# GSMBoard_SIM900.net
KiCad netlist of a schematic drawn in Altium Designer
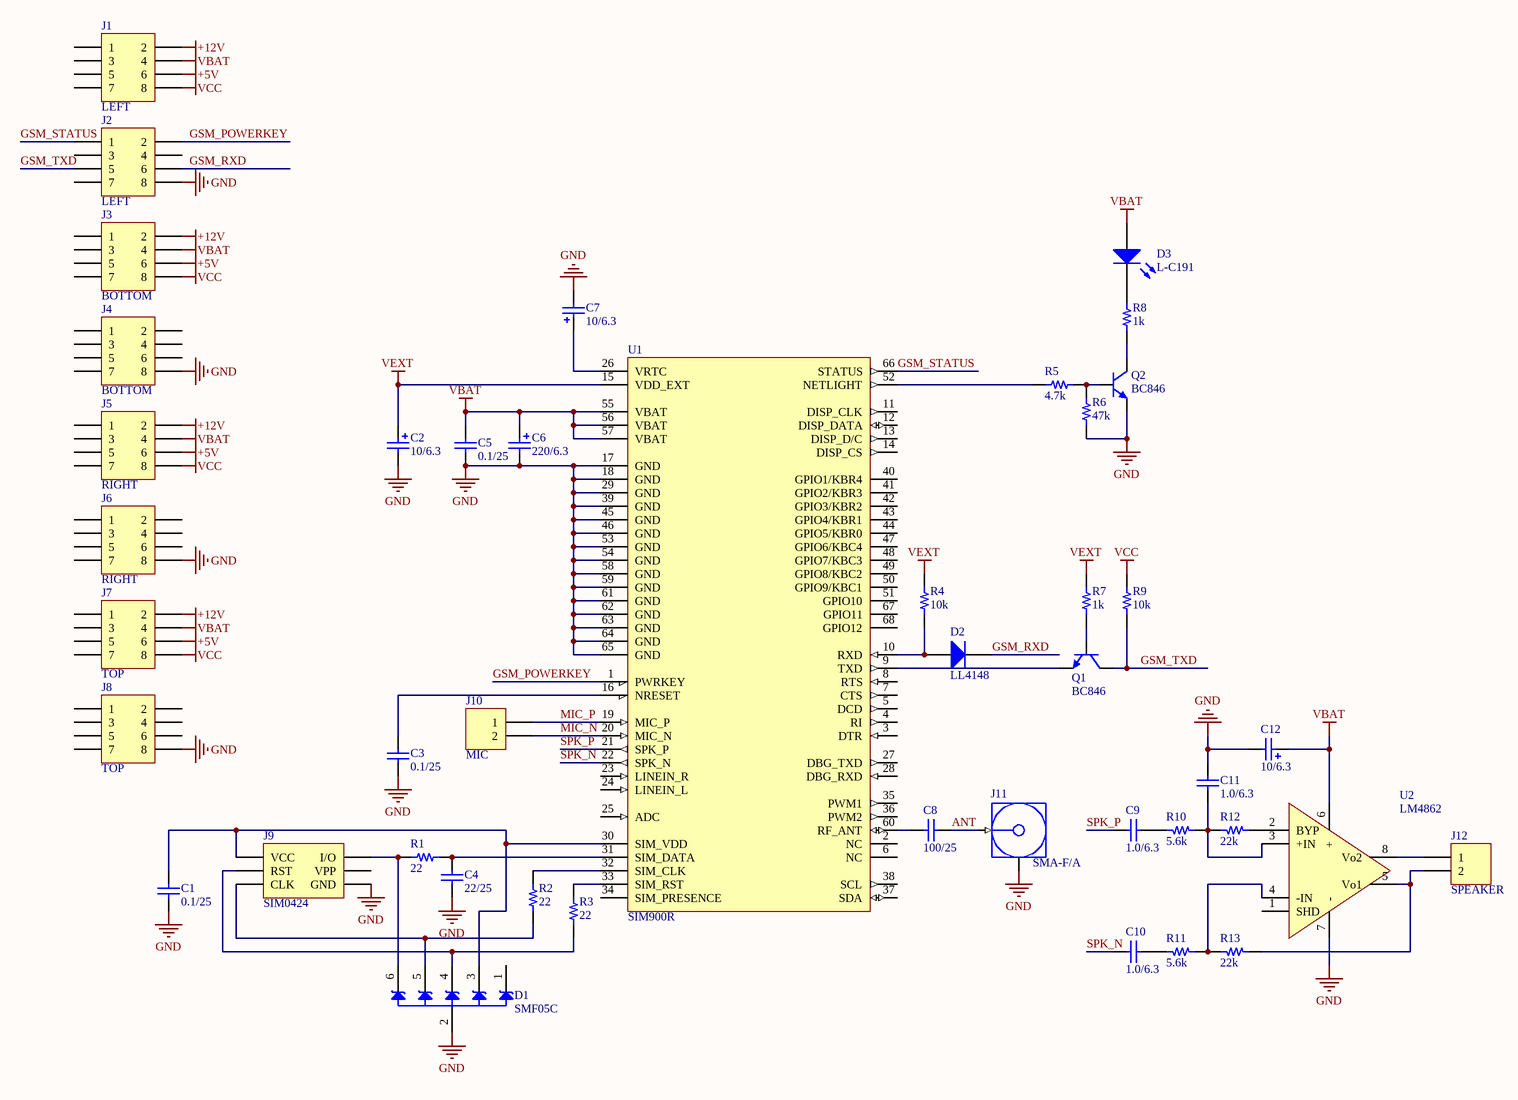
[diagram p0: GSMBoard_SIM900.SchDoc]

(export (version "E")
  (design (tool "Eeschema 10.0.6"))
  (components
    (comp (ref "C1")
      (value "0.1/25")
      (footprint "CAP0402")
      (description "Ceramic chip capacitor 0402")
      (fields
        (field (name "PARTNUMBER") "CAP0402")
        (field (name "VOLTAGE") "25")
        (field (name "AUTHOR") "oiezhov")
      )
      (libsource (lib "Library") (part "Capacitor"))
    )
    (comp (ref "C2")
      (value "10/6.3")
      (footprint "SMA")
      (description "Standard tantalum SMT capacitor, size A")
      (fields
        (field (name "PARTNUMBER") "TAJA")
        (field (name "VOLTAGE") "6.3")
        (field (name "AUTHOR") "oiezhov")
      )
      (libsource (lib "Library") (part "Polar capacitor"))
    )
    (comp (ref "C3")
      (value "0.1/25")
      (footprint "CAP0402")
      (description "Ceramic chip capacitor 0402")
      (fields
        (field (name "PARTNUMBER") "CAP0402")
        (field (name "VOLTAGE") "25")
        (field (name "AUTHOR") "oiezhov")
      )
      (libsource (lib "Library") (part "Capacitor"))
    )
    (comp (ref "C4")
      (value "22/25")
      (footprint "CAP0402")
      (description "Ceramic chip capacitor 0402")
      (fields
        (field (name "PARTNUMBER") "CAP0402")
        (field (name "VOLTAGE") "25")
        (field (name "AUTHOR") "oiezhov")
      )
      (libsource (lib "Library") (part "Capacitor"))
    )
    (comp (ref "C5")
      (value "0.1/25")
      (footprint "CAP0402")
      (description "Ceramic chip capacitor 0402")
      (fields
        (field (name "PARTNUMBER") "CAP0402")
        (field (name "VOLTAGE") "25")
        (field (name "AUTHOR") "oiezhov")
      )
      (libsource (lib "Library") (part "Capacitor"))
    )
    (comp (ref "C6")
      (value "220/6.3")
      (footprint "SMC")
      (description "Standard tantalum SMT capacitor, size C")
      (fields
        (field (name "PARTNUMBER") "TAJC")
        (field (name "VOLTAGE") "6.3")
        (field (name "AUTHOR") "oiezhov")
      )
      (libsource (lib "Library") (part "Polar capacitor"))
    )
    (comp (ref "C7")
      (value "10/6.3")
      (footprint "SMA")
      (description "Standard tantalum SMT capacitor, size A")
      (fields
        (field (name "PARTNUMBER") "TAJA")
        (field (name "VOLTAGE") "6.3")
        (field (name "AUTHOR") "oiezhov")
      )
      (libsource (lib "Library") (part "Polar capacitor"))
    )
    (comp (ref "C8")
      (value "100/25")
      (footprint "CAP0402")
      (description "Ceramic chip capacitor 0402")
      (fields
        (field (name "PARTNUMBER") "CAP0402")
        (field (name "VOLTAGE") "25")
        (field (name "AUTHOR") "oiezhov")
      )
      (libsource (lib "Library") (part "Capacitor"))
    )
    (comp (ref "C9")
      (value "1.0/6.3")
      (footprint "CAP0402")
      (description "Ceramic chip capacitor 0402")
      (fields
        (field (name "PARTNUMBER") "CAP0402")
        (field (name "VOLTAGE") "6.3")
        (field (name "AUTHOR") "oiezhov")
      )
      (libsource (lib "Library") (part "Capacitor"))
    )
    (comp (ref "C10")
      (value "1.0/6.3")
      (footprint "CAP0402")
      (description "Ceramic chip capacitor 0402")
      (fields
        (field (name "PARTNUMBER") "CAP0402")
        (field (name "VOLTAGE") "6.3")
        (field (name "AUTHOR") "oiezhov")
      )
      (libsource (lib "Library") (part "Capacitor"))
    )
    (comp (ref "C11")
      (value "1.0/6.3")
      (footprint "CAP0402")
      (description "Ceramic chip capacitor 0402")
      (fields
        (field (name "PARTNUMBER") "CAP0402")
        (field (name "VOLTAGE") "6.3")
        (field (name "AUTHOR") "oiezhov")
      )
      (libsource (lib "Library") (part "Capacitor"))
    )
    (comp (ref "C12")
      (value "10/6.3")
      (footprint "SMA")
      (description "Standard tantalum SMT capacitor, size A")
      (fields
        (field (name "PARTNUMBER") "TAJA")
        (field (name "VOLTAGE") "6.3")
        (field (name "AUTHOR") "oiezhov")
      )
      (libsource (lib "Library") (part "Polar capacitor"))
    )
    (comp (ref "D1")
      (value "SMF05C")
      (footprint "SOT363")
      (description "5-line TVS Array for ESD and Latch-Up Protection")
      (fields (field (name "AUTHOR") "oiezhov"))
      (libsource (lib "Library") (part "5x TVS array"))
    )
    (comp (ref "D2")
      (value "LL4148")
      (footprint "SOD80")
      (description "Small Signal Diode")
      (fields (field (name "AUTHOR") "oiezhov"))
      (libsource (lib "Library") (part "Diode"))
    )
    (comp (ref "D3")
      (value "L-C191")
      (footprint "LED0603")
      (description "SMD LED, size 0603")
      (fields (field (name "AUTHOR") "oiezhov"))
      (libsource (lib "Library") (part "LED"))
    )
    (comp (ref "J1")
      (value "LEFT")
      (footprint "PBDM-8")
      (description "2x4-pin header, pitch 2.54 mm")
      (fields (field (name "PARTNUMBER") "PBDM-8") (field (name "AUTHOR") "oiezhov"))
      (libsource (lib "Library") (part "8-pin dual row connector"))
    )
    (comp (ref "J2")
      (value "LEFT")
      (footprint "PBDM-8")
      (description "2x4-pin header, pitch 2.54 mm")
      (fields (field (name "PARTNUMBER") "PBDM-8") (field (name "AUTHOR") "oiezhov"))
      (libsource (lib "Library") (part "8-pin dual row connector"))
    )
    (comp (ref "J3")
      (value "BOTTOM")
      (footprint "PBDM-8")
      (description "2x4-pin header, pitch 2.54 mm")
      (fields (field (name "PARTNUMBER") "PBDM-8") (field (name "AUTHOR") "oiezhov"))
      (libsource (lib "Library") (part "8-pin dual row connector"))
    )
    (comp (ref "J4")
      (value "BOTTOM")
      (footprint "PBDM-8")
      (description "2x4-pin header, pitch 2.54 mm")
      (fields (field (name "PARTNUMBER") "PBDM-8") (field (name "AUTHOR") "oiezhov"))
      (libsource (lib "Library") (part "8-pin dual row connector"))
    )
    (comp (ref "J5")
      (value "RIGHT")
      (footprint "PBDM-8")
      (description "2x4-pin header, pitch 2.54 mm")
      (fields (field (name "PARTNUMBER") "PBDM-8") (field (name "AUTHOR") "oiezhov"))
      (libsource (lib "Library") (part "8-pin dual row connector"))
    )
    (comp (ref "J6")
      (value "RIGHT")
      (footprint "PBDM-8")
      (description "2x4-pin header, pitch 2.54 mm")
      (fields (field (name "PARTNUMBER") "PBDM-8") (field (name "AUTHOR") "oiezhov"))
      (libsource (lib "Library") (part "8-pin dual row connector"))
    )
    (comp (ref "J7")
      (value "TOP")
      (footprint "PBDM-8")
      (description "2x4-pin header, pitch 2.54 mm")
      (fields (field (name "PARTNUMBER") "PBDM-8") (field (name "AUTHOR") "oiezhov"))
      (libsource (lib "Library") (part "8-pin dual row connector"))
    )
    (comp (ref "J8")
      (value "TOP")
      (footprint "PBDM-8")
      (description "2x4-pin header, pitch 2.54 mm")
      (fields (field (name "PARTNUMBER") "PBDM-8") (field (name "AUTHOR") "oiezhov"))
      (libsource (lib "Library") (part "8-pin dual row connector"))
    )
    (comp (ref "J9")
      (value "SIM0424")
      (footprint "SIM0424")
      (description "6-pin SIM card holder")
      (fields (field (name "AUTHOR") "oiezhov"))
      (libsource (lib "Library") (part "6-pin SIM holder"))
    )
    (comp (ref "J10")
      (value "MIC")
      (footprint "PLS-2R")
      (description "2-pin angle header, pitch 2.54 mm")
      (fields (field (name "PARTNUMBER") "PLS-2R") (field (name "AUTHOR") "oiezhov"))
      (libsource (lib "") (part "2-pin connector_1"))
    )
    (comp (ref "J11")
      (value "SMA-F/A")
      (footprint "SMA-F/A")
      (description "Angle SMA female connector")
      (fields (field (name "AUTHOR") "oiezhov"))
      (libsource (lib "Library") (part "SMA"))
    )
    (comp (ref "J12")
      (value "SPEAKER")
      (footprint "PLS-2R")
      (description "2-pin angle header, pitch 2.54 mm")
      (fields (field (name "PARTNUMBER") "PLS-2R") (field (name "AUTHOR") "oiezhov"))
      (libsource (lib "Library") (part "2-pin connector"))
    )
    (comp (ref "Q1")
      (value "BC846")
      (footprint "SOT23")
      (description "NPN Silicon AF Transistor")
      (fields (field (name "AUTHOR") "oiezhov"))
      (libsource (lib "Library") (part "NPN Transistor (B-E-C)"))
    )
    (comp (ref "Q2")
      (value "BC846")
      (footprint "SOT23")
      (description "NPN Silicon AF Transistor")
      (fields (field (name "AUTHOR") "oiezhov"))
      (libsource (lib "Library") (part "NPN Transistor (B-E-C)"))
    )
    (comp (ref "R1")
      (value "22")
      (footprint "RES0402")
      (description "Ceramic chip resistor")
      (fields (field (name "PARTNUMBER") "RES0402") (field (name "AUTHOR") "oiezhov"))
      (libsource (lib "Library") (part "Resistor"))
    )
    (comp (ref "R2")
      (value "22")
      (footprint "RES0402")
      (description "Ceramic chip resistor")
      (fields (field (name "PARTNUMBER") "RES0402") (field (name "AUTHOR") "oiezhov"))
      (libsource (lib "Library") (part "Resistor"))
    )
    (comp (ref "R3")
      (value "22")
      (footprint "RES0402")
      (description "Ceramic chip resistor")
      (fields (field (name "PARTNUMBER") "RES0402") (field (name "AUTHOR") "oiezhov"))
      (libsource (lib "Library") (part "Resistor"))
    )
    (comp (ref "R4")
      (value "10k")
      (footprint "RES0402")
      (description "Ceramic chip resistor")
      (fields (field (name "PARTNUMBER") "RES0402") (field (name "AUTHOR") "oiezhov"))
      (libsource (lib "Library") (part "Resistor"))
    )
    (comp (ref "R5")
      (value "4.7k")
      (footprint "RES0402")
      (description "Ceramic chip resistor")
      (fields (field (name "PARTNUMBER") "RES0402") (field (name "AUTHOR") "oiezhov"))
      (libsource (lib "Library") (part "Resistor"))
    )
    (comp (ref "R6")
      (value "47k")
      (footprint "RES0402")
      (description "Ceramic chip resistor")
      (fields (field (name "PARTNUMBER") "RES0402") (field (name "AUTHOR") "oiezhov"))
      (libsource (lib "Library") (part "Resistor"))
    )
    (comp (ref "R7")
      (value "1k")
      (footprint "RES0402")
      (description "Ceramic chip resistor")
      (fields (field (name "PARTNUMBER") "RES0402") (field (name "AUTHOR") "oiezhov"))
      (libsource (lib "Library") (part "Resistor"))
    )
    (comp (ref "R8")
      (value "1k")
      (footprint "RES0402")
      (description "Ceramic chip resistor")
      (fields (field (name "PARTNUMBER") "RES0402") (field (name "AUTHOR") "oiezhov"))
      (libsource (lib "Library") (part "Resistor"))
    )
    (comp (ref "R9")
      (value "10k")
      (footprint "RES0402")
      (description "Ceramic chip resistor")
      (fields (field (name "PARTNUMBER") "RES0402") (field (name "AUTHOR") "oiezhov"))
      (libsource (lib "Library") (part "Resistor"))
    )
    (comp (ref "R10")
      (value "5.6k")
      (footprint "RES0402")
      (description "Ceramic chip resistor")
      (fields (field (name "PARTNUMBER") "RES0402") (field (name "AUTHOR") "oiezhov"))
      (libsource (lib "Library") (part "Resistor"))
    )
    (comp (ref "R11")
      (value "5.6k")
      (footprint "RES0402")
      (description "Ceramic chip resistor")
      (fields (field (name "PARTNUMBER") "RES0402") (field (name "AUTHOR") "oiezhov"))
      (libsource (lib "Library") (part "Resistor"))
    )
    (comp (ref "R12")
      (value "22k")
      (footprint "RES0402")
      (description "Ceramic chip resistor")
      (fields (field (name "PARTNUMBER") "RES0402") (field (name "AUTHOR") "oiezhov"))
      (libsource (lib "Library") (part "Resistor"))
    )
    (comp (ref "R13")
      (value "22k")
      (footprint "RES0402")
      (description "Ceramic chip resistor")
      (fields (field (name "PARTNUMBER") "RES0402") (field (name "AUTHOR") "oiezhov"))
      (libsource (lib "Library") (part "Resistor"))
    )
    (comp (ref "U1")
      (value "SIM900R")
      (footprint "SIM900_quad68")
      (description "GSM module; 2G; 1800MHz,900MHz; 85.6kbps; I2C, UART; 3.4A@4.5VDC")
      (fields (field (name "AUTHOR") "oiezhov"))
      (libsource (lib "Library") (part "SIM900"))
    )
    (comp (ref "U2")
      (value "LM4862")
      (footprint "SO8")
      (description "Audio Power Amplifier with Shutdown Mode")
      (fields (field (name "AUTHOR") "oiezhov"))
      (libsource (lib "Library") (part "LM4862"))
    )
  )
  (nets
    (net (code "1") (name "+5V") (class "Default")
      (node (ref "J1") (pin "6") (pinfunction "6_6") (pintype "passive"))
      (node (ref "J3") (pin "6") (pinfunction "6_6") (pintype "passive"))
      (node (ref "J5") (pin "6") (pinfunction "6_6") (pintype "passive"))
      (node (ref "J7") (pin "6") (pinfunction "6_6") (pintype "passive"))
    )
    (net (code "2") (name "+12V") (class "Default")
      (node (ref "J1") (pin "2") (pinfunction "2_2") (pintype "passive"))
      (node (ref "J3") (pin "2") (pinfunction "2_2") (pintype "passive"))
      (node (ref "J5") (pin "2") (pinfunction "2_2") (pintype "passive"))
      (node (ref "J7") (pin "2") (pinfunction "2_2") (pintype "passive"))
    )
    (net (code "3") (name "/ANT") (class "Default")
      (node (ref "C8") (pin "2") (pinfunction "2_2") (pintype "passive"))
      (node (ref "J11") (pin "1") (pinfunction "Signal_1") (pintype "input"))
    )
    (net (code "4") (name "/GSM_POWERKEY") (class "Default")
      (node (ref "J2") (pin "2") (pinfunction "2_2") (pintype "passive"))
      (node (ref "U1") (pin "1") (pinfunction "PWRKEY_1") (pintype "passive"))
    )
    (net (code "5") (name "/GSM_RXD") (class "Default")
      (node (ref "D2") (pin "1") (pinfunction "1_1") (pintype "passive"))
      (node (ref "J2") (pin "6") (pinfunction "6_6") (pintype "passive"))
    )
    (net (code "6") (name "/GSM_STATUS") (class "Default")
      (node (ref "J2") (pin "1") (pinfunction "1_1") (pintype "passive"))
      (node (ref "U1") (pin "66") (pinfunction "STATUS_66") (pintype "output"))
    )
    (net (code "7") (name "/GSM_TXD") (class "Default")
      (node (ref "J2") (pin "5") (pinfunction "5_5") (pintype "passive"))
      (node (ref "Q1") (pin "3") (pinfunction "3_3") (pintype "passive"))
      (node (ref "R9") (pin "2") (pinfunction "2_2") (pintype "passive"))
    )
    (net (code "8") (name "/MIC_N") (class "Default")
      (node (ref "J10") (pin "2") (pinfunction "2_2") (pintype "passive"))
      (node (ref "U1") (pin "20") (pinfunction "MIC_N_20") (pintype "input"))
    )
    (net (code "9") (name "/MIC_P") (class "Default")
      (node (ref "J10") (pin "1") (pinfunction "1_1") (pintype "passive"))
      (node (ref "U1") (pin "19") (pinfunction "MIC_P_19") (pintype "input"))
    )
    (net (code "10") (name "/SPK_N") (class "Default")
      (node (ref "C10") (pin "1") (pinfunction "1_1") (pintype "passive"))
      (node (ref "U1") (pin "22") (pinfunction "SPK_N_22") (pintype "output"))
    )
    (net (code "11") (name "/SPK_P") (class "Default")
      (node (ref "C9") (pin "1") (pinfunction "1_1") (pintype "passive"))
      (node (ref "U1") (pin "21") (pinfunction "SPK_P_21") (pintype "output"))
    )
    (net (code "12") (name "GND") (class "Default")
      (node (ref "C1") (pin "1") (pinfunction "1_1") (pintype "passive"))
      (node (ref "C11") (pin "1") (pinfunction "1_1") (pintype "passive"))
      (node (ref "C12") (pin "1") (pinfunction "1_1") (pintype "passive"))
      (node (ref "C2") (pin "1") (pinfunction "1_1") (pintype "passive"))
      (node (ref "C3") (pin "1") (pinfunction "1_1") (pintype "passive"))
      (node (ref "C4") (pin "1") (pinfunction "1_1") (pintype "passive"))
      (node (ref "C5") (pin "1") (pinfunction "1_1") (pintype "passive"))
      (node (ref "C6") (pin "1") (pinfunction "1_1") (pintype "passive"))
      (node (ref "C7") (pin "1") (pinfunction "1_1") (pintype "passive"))
      (node (ref "D1") (pin "2") (pinfunction "2_2") (pintype "passive"))
      (node (ref "J11") (pin "2") (pinfunction "GND_2") (pintype "power_in"))
      (node (ref "J2") (pin "8") (pinfunction "8_8") (pintype "passive"))
      (node (ref "J4") (pin "8") (pinfunction "8_8") (pintype "passive"))
      (node (ref "J6") (pin "8") (pinfunction "8_8") (pintype "passive"))
      (node (ref "J8") (pin "8") (pinfunction "8_8") (pintype "passive"))
      (node (ref "J9") (pin "4") (pinfunction "GND_4") (pintype "passive"))
      (node (ref "Q2") (pin "2") (pinfunction "2_2") (pintype "passive"))
      (node (ref "R6") (pin "2") (pinfunction "2_2") (pintype "passive"))
      (node (ref "U1") (pin "17") (pinfunction "GND_17") (pintype "passive"))
      (node (ref "U1") (pin "18") (pinfunction "GND_18") (pintype "passive"))
      (node (ref "U1") (pin "29") (pinfunction "GND_29") (pintype "passive"))
      (node (ref "U1") (pin "39") (pinfunction "GND_39") (pintype "passive"))
      (node (ref "U1") (pin "45") (pinfunction "GND_45") (pintype "passive"))
      (node (ref "U1") (pin "46") (pinfunction "GND_46") (pintype "passive"))
      (node (ref "U1") (pin "53") (pinfunction "GND_53") (pintype "passive"))
      (node (ref "U1") (pin "54") (pinfunction "GND_54") (pintype "passive"))
      (node (ref "U1") (pin "58") (pinfunction "GND_58") (pintype "passive"))
      (node (ref "U1") (pin "59") (pinfunction "GND_59") (pintype "passive"))
      (node (ref "U1") (pin "61") (pinfunction "GND_61") (pintype "passive"))
      (node (ref "U1") (pin "62") (pinfunction "GND_62") (pintype "passive"))
      (node (ref "U1") (pin "63") (pinfunction "GND_63") (pintype "passive"))
      (node (ref "U1") (pin "64") (pinfunction "GND_64") (pintype "passive"))
      (node (ref "U1") (pin "65") (pinfunction "GND_65") (pintype "passive"))
      (node (ref "U2") (pin "7") (pinfunction "-_7") (pintype "power_in"))
    )
    (net (code "13") (name "Net-(C9-Pad2)") (class "Default")
      (node (ref "C9") (pin "2") (pinfunction "2_2") (pintype "passive"))
      (node (ref "R10") (pin "2") (pinfunction "2_2") (pintype "passive"))
    )
    (net (code "14") (name "Net-(C10-Pad2)") (class "Default")
      (node (ref "C10") (pin "2") (pinfunction "2_2") (pintype "passive"))
      (node (ref "R11") (pin "2") (pinfunction "2_2") (pintype "passive"))
    )
    (net (code "15") (name "Net-(D3-Pad1)") (class "Default")
      (node (ref "D3") (pin "1") (pinfunction "1_1") (pintype "passive"))
      (node (ref "R8") (pin "1") (pinfunction "1_1") (pintype "passive"))
    )
    (net (code "16") (name "Net-(J9-CLK)") (class "Default")
      (node (ref "D1") (pin "5") (pinfunction "5_5") (pintype "passive"))
      (node (ref "J9") (pin "3") (pinfunction "CLK_3") (pintype "passive"))
      (node (ref "R2") (pin "2") (pinfunction "2_2") (pintype "passive"))
    )
    (net (code "17") (name "Net-(J9-I{slash}O)") (class "Default")
      (node (ref "D1") (pin "6") (pinfunction "6_6") (pintype "passive"))
      (node (ref "J9") (pin "6") (pinfunction "I/O_6") (pintype "passive"))
      (node (ref "R1") (pin "2") (pinfunction "2_2") (pintype "passive"))
    )
    (net (code "18") (name "Net-(J9-RST)") (class "Default")
      (node (ref "D1") (pin "4") (pinfunction "4_4") (pintype "passive"))
      (node (ref "J9") (pin "2") (pinfunction "RST_2") (pintype "passive"))
      (node (ref "R3") (pin "2") (pinfunction "2_2") (pintype "passive"))
    )
    (net (code "19") (name "Net-(J9-VCC)") (class "Default")
      (node (ref "C1") (pin "2") (pinfunction "2_2") (pintype "passive"))
      (node (ref "D1") (pin "3") (pinfunction "3_3") (pintype "passive"))
      (node (ref "J9") (pin "1") (pinfunction "VCC_1") (pintype "passive"))
      (node (ref "U1") (pin "30") (pinfunction "SIM_VDD_30") (pintype "passive"))
    )
    (net (code "20") (name "Net-(Q1-Pad1)") (class "Default")
      (node (ref "Q1") (pin "1") (pinfunction "1_1") (pintype "passive"))
      (node (ref "R7") (pin "2") (pinfunction "2_2") (pintype "passive"))
    )
    (net (code "21") (name "Net-(Q2-Pad1)") (class "Default")
      (node (ref "Q2") (pin "1") (pinfunction "1_1") (pintype "passive"))
      (node (ref "R5") (pin "1") (pinfunction "1_1") (pintype "passive"))
      (node (ref "R6") (pin "1") (pinfunction "1_1") (pintype "passive"))
    )
    (net (code "22") (name "Net-(Q2-Pad3)") (class "Default")
      (node (ref "Q2") (pin "3") (pinfunction "3_3") (pintype "passive"))
      (node (ref "R8") (pin "2") (pinfunction "2_2") (pintype "passive"))
    )
    (net (code "23") (name "Net-(U1-NETLIGHT)") (class "Default")
      (node (ref "R5") (pin "2") (pinfunction "2_2") (pintype "passive"))
      (node (ref "U1") (pin "52") (pinfunction "NETLIGHT_52") (pintype "output"))
    )
    (net (code "24") (name "Net-(U1-NRESET)") (class "Default")
      (node (ref "C3") (pin "2") (pinfunction "2_2") (pintype "passive"))
      (node (ref "U1") (pin "16") (pinfunction "NRESET_16") (pintype "passive"))
    )
    (net (code "25") (name "Net-(U1-RF_ANT)") (class "Default")
      (node (ref "C8") (pin "1") (pinfunction "1_1") (pintype "passive"))
      (node (ref "U1") (pin "60") (pinfunction "RF_ANT_60") (pintype "bidirectional"))
    )
    (net (code "26") (name "Net-(U1-RXD)") (class "Default")
      (node (ref "D2") (pin "2") (pinfunction "2_2") (pintype "passive"))
      (node (ref "R4") (pin "2") (pinfunction "2_2") (pintype "passive"))
      (node (ref "U1") (pin "10") (pinfunction "RXD_10") (pintype "input"))
    )
    (net (code "27") (name "Net-(U1-SIM_CLK)") (class "Default")
      (node (ref "R2") (pin "1") (pinfunction "1_1") (pintype "passive"))
      (node (ref "U1") (pin "32") (pinfunction "SIM_CLK_32") (pintype "passive"))
    )
    (net (code "28") (name "Net-(U1-SIM_DATA)") (class "Default")
      (node (ref "C4") (pin "2") (pinfunction "2_2") (pintype "passive"))
      (node (ref "R1") (pin "1") (pinfunction "1_1") (pintype "passive"))
      (node (ref "U1") (pin "31") (pinfunction "SIM_DATA_31") (pintype "passive"))
    )
    (net (code "29") (name "Net-(U1-SIM_RST)") (class "Default")
      (node (ref "R3") (pin "1") (pinfunction "1_1") (pintype "passive"))
      (node (ref "U1") (pin "33") (pinfunction "SIM_RST_33") (pintype "passive"))
    )
    (net (code "30") (name "Net-(U1-TXD)") (class "Default")
      (node (ref "Q1") (pin "2") (pinfunction "2_2") (pintype "passive"))
      (node (ref "U1") (pin "9") (pinfunction "TXD_9") (pintype "output"))
    )
    (net (code "31") (name "Net-(U1-VRTC)") (class "Default")
      (node (ref "C7") (pin "2") (pinfunction "2_2") (pintype "passive"))
      (node (ref "U1") (pin "26") (pinfunction "VRTC_26") (pintype "power_in"))
    )
    (net (code "32") (name "Net-(U2-+IN)") (class "Default")
      (node (ref "C11") (pin "2") (pinfunction "2_2") (pintype "passive"))
      (node (ref "R10") (pin "1") (pinfunction "1_1") (pintype "passive"))
      (node (ref "R12") (pin "2") (pinfunction "2_2") (pintype "passive"))
      (node (ref "U2") (pin "3") (pinfunction "+IN_3") (pintype "passive"))
    )
    (net (code "33") (name "Net-(U2--IN)") (class "Default")
      (node (ref "R11") (pin "1") (pinfunction "1_1") (pintype "passive"))
      (node (ref "R13") (pin "2") (pinfunction "2_2") (pintype "passive"))
      (node (ref "U2") (pin "4") (pinfunction "-IN_4") (pintype "passive"))
    )
    (net (code "34") (name "Net-(U2-BYP)") (class "Default")
      (node (ref "R12") (pin "1") (pinfunction "1_1") (pintype "passive"))
      (node (ref "U2") (pin "2") (pinfunction "BYP_2") (pintype "passive"))
    )
    (net (code "35") (name "Net-(U2-Vo1)") (class "Default")
      (node (ref "J12") (pin "2") (pinfunction "2_2") (pintype "passive"))
      (node (ref "R13") (pin "1") (pinfunction "1_1") (pintype "passive"))
      (node (ref "U2") (pin "5") (pinfunction "Vo1_5") (pintype "passive"))
    )
    (net (code "36") (name "Net-(U2-Vo2)") (class "Default")
      (node (ref "J12") (pin "1") (pinfunction "1_1") (pintype "passive"))
      (node (ref "U2") (pin "8") (pinfunction "Vo2_8") (pintype "passive"))
    )
    (net (code "37") (name "VBAT") (class "Default")
      (node (ref "C12") (pin "2") (pinfunction "2_2") (pintype "passive"))
      (node (ref "C5") (pin "2") (pinfunction "2_2") (pintype "passive"))
      (node (ref "C6") (pin "2") (pinfunction "2_2") (pintype "passive"))
      (node (ref "D3") (pin "2") (pinfunction "2_2") (pintype "passive"))
      (node (ref "J1") (pin "4") (pinfunction "4_4") (pintype "passive"))
      (node (ref "J3") (pin "4") (pinfunction "4_4") (pintype "passive"))
      (node (ref "J5") (pin "4") (pinfunction "4_4") (pintype "passive"))
      (node (ref "J7") (pin "4") (pinfunction "4_4") (pintype "passive"))
      (node (ref "U1") (pin "55") (pinfunction "VBAT_55") (pintype "power_in"))
      (node (ref "U1") (pin "56") (pinfunction "VBAT_56") (pintype "power_in"))
      (node (ref "U1") (pin "57") (pinfunction "VBAT_57") (pintype "power_in"))
      (node (ref "U2") (pin "6") (pinfunction "+_6") (pintype "power_in"))
    )
    (net (code "38") (name "VCC") (class "Default")
      (node (ref "J1") (pin "8") (pinfunction "8_8") (pintype "passive"))
      (node (ref "J3") (pin "8") (pinfunction "8_8") (pintype "passive"))
      (node (ref "J5") (pin "8") (pinfunction "8_8") (pintype "passive"))
      (node (ref "J7") (pin "8") (pinfunction "8_8") (pintype "passive"))
      (node (ref "R9") (pin "1") (pinfunction "1_1") (pintype "passive"))
    )
    (net (code "39") (name "VEXT") (class "Default")
      (node (ref "C2") (pin "2") (pinfunction "2_2") (pintype "passive"))
      (node (ref "R4") (pin "1") (pinfunction "1_1") (pintype "passive"))
      (node (ref "R7") (pin "1") (pinfunction "1_1") (pintype "passive"))
      (node (ref "U1") (pin "15") (pinfunction "VDD_EXT_15") (pintype "power_in"))
    )
    (net (code "40") (name "unconnected-(D1-Pad1)") (class "Default")
      (node (ref "D1") (pin "1") (pinfunction "1_1") (pintype "passive"))
    )
    (net (code "41") (name "unconnected-(J1-Pad1)") (class "Default")
      (node (ref "J1") (pin "1") (pinfunction "1_1") (pintype "passive"))
    )
    (net (code "42") (name "unconnected-(J1-Pad3)") (class "Default")
      (node (ref "J1") (pin "3") (pinfunction "3_3") (pintype "passive"))
    )
    (net (code "43") (name "unconnected-(J1-Pad5)") (class "Default")
      (node (ref "J1") (pin "5") (pinfunction "5_5") (pintype "passive"))
    )
    (net (code "44") (name "unconnected-(J1-Pad7)") (class "Default")
      (node (ref "J1") (pin "7") (pinfunction "7_7") (pintype "passive"))
    )
    (net (code "45") (name "unconnected-(J2-Pad3)") (class "Default")
      (node (ref "J2") (pin "3") (pinfunction "3_3") (pintype "passive"))
    )
    (net (code "46") (name "unconnected-(J2-Pad4)") (class "Default")
      (node (ref "J2") (pin "4") (pinfunction "4_4") (pintype "passive"))
    )
    (net (code "47") (name "unconnected-(J2-Pad7)") (class "Default")
      (node (ref "J2") (pin "7") (pinfunction "7_7") (pintype "passive"))
    )
    (net (code "48") (name "unconnected-(J3-Pad1)") (class "Default")
      (node (ref "J3") (pin "1") (pinfunction "1_1") (pintype "passive"))
    )
    (net (code "49") (name "unconnected-(J3-Pad3)") (class "Default")
      (node (ref "J3") (pin "3") (pinfunction "3_3") (pintype "passive"))
    )
    (net (code "50") (name "unconnected-(J3-Pad5)") (class "Default")
      (node (ref "J3") (pin "5") (pinfunction "5_5") (pintype "passive"))
    )
    (net (code "51") (name "unconnected-(J3-Pad7)") (class "Default")
      (node (ref "J3") (pin "7") (pinfunction "7_7") (pintype "passive"))
    )
    (net (code "52") (name "unconnected-(J4-Pad1)") (class "Default")
      (node (ref "J4") (pin "1") (pinfunction "1_1") (pintype "passive"))
    )
    (net (code "53") (name "unconnected-(J4-Pad2)") (class "Default")
      (node (ref "J4") (pin "2") (pinfunction "2_2") (pintype "passive"))
    )
    (net (code "54") (name "unconnected-(J4-Pad3)") (class "Default")
      (node (ref "J4") (pin "3") (pinfunction "3_3") (pintype "passive"))
    )
    (net (code "55") (name "unconnected-(J4-Pad4)") (class "Default")
      (node (ref "J4") (pin "4") (pinfunction "4_4") (pintype "passive"))
    )
    (net (code "56") (name "unconnected-(J4-Pad5)") (class "Default")
      (node (ref "J4") (pin "5") (pinfunction "5_5") (pintype "passive"))
    )
    (net (code "57") (name "unconnected-(J4-Pad6)") (class "Default")
      (node (ref "J4") (pin "6") (pinfunction "6_6") (pintype "passive"))
    )
    (net (code "58") (name "unconnected-(J4-Pad7)") (class "Default")
      (node (ref "J4") (pin "7") (pinfunction "7_7") (pintype "passive"))
    )
    (net (code "59") (name "unconnected-(J5-Pad1)") (class "Default")
      (node (ref "J5") (pin "1") (pinfunction "1_1") (pintype "passive"))
    )
    (net (code "60") (name "unconnected-(J5-Pad3)") (class "Default")
      (node (ref "J5") (pin "3") (pinfunction "3_3") (pintype "passive"))
    )
    (net (code "61") (name "unconnected-(J5-Pad5)") (class "Default")
      (node (ref "J5") (pin "5") (pinfunction "5_5") (pintype "passive"))
    )
    (net (code "62") (name "unconnected-(J5-Pad7)") (class "Default")
      (node (ref "J5") (pin "7") (pinfunction "7_7") (pintype "passive"))
    )
    (net (code "63") (name "unconnected-(J6-Pad1)") (class "Default")
      (node (ref "J6") (pin "1") (pinfunction "1_1") (pintype "passive"))
    )
    (net (code "64") (name "unconnected-(J6-Pad2)") (class "Default")
      (node (ref "J6") (pin "2") (pinfunction "2_2") (pintype "passive"))
    )
    (net (code "65") (name "unconnected-(J6-Pad3)") (class "Default")
      (node (ref "J6") (pin "3") (pinfunction "3_3") (pintype "passive"))
    )
    (net (code "66") (name "unconnected-(J6-Pad4)") (class "Default")
      (node (ref "J6") (pin "4") (pinfunction "4_4") (pintype "passive"))
    )
    (net (code "67") (name "unconnected-(J6-Pad5)") (class "Default")
      (node (ref "J6") (pin "5") (pinfunction "5_5") (pintype "passive"))
    )
    (net (code "68") (name "unconnected-(J6-Pad6)") (class "Default")
      (node (ref "J6") (pin "6") (pinfunction "6_6") (pintype "passive"))
    )
    (net (code "69") (name "unconnected-(J6-Pad7)") (class "Default")
      (node (ref "J6") (pin "7") (pinfunction "7_7") (pintype "passive"))
    )
    (net (code "70") (name "unconnected-(J7-Pad1)") (class "Default")
      (node (ref "J7") (pin "1") (pinfunction "1_1") (pintype "passive"))
    )
    (net (code "71") (name "unconnected-(J7-Pad3)") (class "Default")
      (node (ref "J7") (pin "3") (pinfunction "3_3") (pintype "passive"))
    )
    (net (code "72") (name "unconnected-(J7-Pad5)") (class "Default")
      (node (ref "J7") (pin "5") (pinfunction "5_5") (pintype "passive"))
    )
    (net (code "73") (name "unconnected-(J7-Pad7)") (class "Default")
      (node (ref "J7") (pin "7") (pinfunction "7_7") (pintype "passive"))
    )
    (net (code "74") (name "unconnected-(J8-Pad1)") (class "Default")
      (node (ref "J8") (pin "1") (pinfunction "1_1") (pintype "passive"))
    )
    (net (code "75") (name "unconnected-(J8-Pad2)") (class "Default")
      (node (ref "J8") (pin "2") (pinfunction "2_2") (pintype "passive"))
    )
    (net (code "76") (name "unconnected-(J8-Pad3)") (class "Default")
      (node (ref "J8") (pin "3") (pinfunction "3_3") (pintype "passive"))
    )
    (net (code "77") (name "unconnected-(J8-Pad4)") (class "Default")
      (node (ref "J8") (pin "4") (pinfunction "4_4") (pintype "passive"))
    )
    (net (code "78") (name "unconnected-(J8-Pad5)") (class "Default")
      (node (ref "J8") (pin "5") (pinfunction "5_5") (pintype "passive"))
    )
    (net (code "79") (name "unconnected-(J8-Pad6)") (class "Default")
      (node (ref "J8") (pin "6") (pinfunction "6_6") (pintype "passive"))
    )
    (net (code "80") (name "unconnected-(J8-Pad7)") (class "Default")
      (node (ref "J8") (pin "7") (pinfunction "7_7") (pintype "passive"))
    )
    (net (code "81") (name "unconnected-(J9-VPP-Pad5)") (class "Default")
      (node (ref "J9") (pin "5") (pinfunction "VPP_5") (pintype "passive"))
    )
    (net (code "82") (name "unconnected-(U1-ADC-Pad25)") (class "Default")
      (node (ref "U1") (pin "25") (pinfunction "ADC_25") (pintype "input"))
    )
    (net (code "83") (name "unconnected-(U1-CTS-Pad7)") (class "Default")
      (node (ref "U1") (pin "7") (pinfunction "CTS_7") (pintype "output"))
    )
    (net (code "84") (name "unconnected-(U1-DBG_RXD-Pad28)") (class "Default")
      (node (ref "U1") (pin "28") (pinfunction "DBG_RXD_28") (pintype "input"))
    )
    (net (code "85") (name "unconnected-(U1-DBG_TXD-Pad27)") (class "Default")
      (node (ref "U1") (pin "27") (pinfunction "DBG_TXD_27") (pintype "output"))
    )
    (net (code "86") (name "unconnected-(U1-DCD-Pad5)") (class "Default")
      (node (ref "U1") (pin "5") (pinfunction "DCD_5") (pintype "output"))
    )
    (net (code "87") (name "unconnected-(U1-DISP_CLK-Pad11)") (class "Default")
      (node (ref "U1") (pin "11") (pinfunction "DISP_CLK_11") (pintype "output"))
    )
    (net (code "88") (name "unconnected-(U1-DISP_CS-Pad14)") (class "Default")
      (node (ref "U1") (pin "14") (pinfunction "DISP_CS_14") (pintype "output"))
    )
    (net (code "89") (name "unconnected-(U1-DISP_DATA-Pad12)") (class "Default")
      (node (ref "U1") (pin "12") (pinfunction "DISP_DATA_12") (pintype "bidirectional"))
    )
    (net (code "90") (name "unconnected-(U1-DISP_D{slash}C-Pad13)") (class "Default")
      (node (ref "U1") (pin "13") (pinfunction "DISP_D/C_13") (pintype "output"))
    )
    (net (code "91") (name "unconnected-(U1-DTR-Pad3)") (class "Default")
      (node (ref "U1") (pin "3") (pinfunction "DTR_3") (pintype "input"))
    )
    (net (code "92") (name "unconnected-(U1-GPIO1{slash}KBR4-Pad40)") (class "Default")
      (node (ref "U1") (pin "40") (pinfunction "GPIO1/KBR4_40") (pintype "passive"))
    )
    (net (code "93") (name "unconnected-(U1-GPIO2{slash}KBR3-Pad41)") (class "Default")
      (node (ref "U1") (pin "41") (pinfunction "GPIO2/KBR3_41") (pintype "passive"))
    )
    (net (code "94") (name "unconnected-(U1-GPIO3{slash}KBR2-Pad42)") (class "Default")
      (node (ref "U1") (pin "42") (pinfunction "GPIO3/KBR2_42") (pintype "passive"))
    )
    (net (code "95") (name "unconnected-(U1-GPIO4{slash}KBR1-Pad43)") (class "Default")
      (node (ref "U1") (pin "43") (pinfunction "GPIO4/KBR1_43") (pintype "passive"))
    )
    (net (code "96") (name "unconnected-(U1-GPIO5{slash}KBR0-Pad44)") (class "Default")
      (node (ref "U1") (pin "44") (pinfunction "GPIO5/KBR0_44") (pintype "passive"))
    )
    (net (code "97") (name "unconnected-(U1-GPIO6{slash}KBC4-Pad47)") (class "Default")
      (node (ref "U1") (pin "47") (pinfunction "GPIO6/KBC4_47") (pintype "passive"))
    )
    (net (code "98") (name "unconnected-(U1-GPIO7{slash}KBC3-Pad48)") (class "Default")
      (node (ref "U1") (pin "48") (pinfunction "GPIO7/KBC3_48") (pintype "passive"))
    )
    (net (code "99") (name "unconnected-(U1-GPIO8{slash}KBC2-Pad49)") (class "Default")
      (node (ref "U1") (pin "49") (pinfunction "GPIO8/KBC2_49") (pintype "passive"))
    )
    (net (code "100") (name "unconnected-(U1-GPIO9{slash}KBC1-Pad50)") (class "Default")
      (node (ref "U1") (pin "50") (pinfunction "GPIO9/KBC1_50") (pintype "passive"))
    )
    (net (code "101") (name "unconnected-(U1-GPIO10-Pad51)") (class "Default")
      (node (ref "U1") (pin "51") (pinfunction "GPIO10_51") (pintype "passive"))
    )
    (net (code "102") (name "unconnected-(U1-GPIO11-Pad67)") (class "Default")
      (node (ref "U1") (pin "67") (pinfunction "GPIO11_67") (pintype "passive"))
    )
    (net (code "103") (name "unconnected-(U1-GPIO12-Pad68)") (class "Default")
      (node (ref "U1") (pin "68") (pinfunction "GPIO12_68") (pintype "passive"))
    )
    (net (code "104") (name "unconnected-(U1-LINEIN_L-Pad24)") (class "Default")
      (node (ref "U1") (pin "24") (pinfunction "LINEIN_L_24") (pintype "input"))
    )
    (net (code "105") (name "unconnected-(U1-LINEIN_R-Pad23)") (class "Default")
      (node (ref "U1") (pin "23") (pinfunction "LINEIN_R_23") (pintype "input"))
    )
    (net (code "106") (name "unconnected-(U1-NC-Pad2)") (class "Default")
      (node (ref "U1") (pin "2") (pinfunction "NC_2") (pintype "passive"))
    )
    (net (code "107") (name "unconnected-(U1-NC-Pad6)") (class "Default")
      (node (ref "U1") (pin "6") (pinfunction "NC_6") (pintype "passive"))
    )
    (net (code "108") (name "unconnected-(U1-PWM1-Pad35)") (class "Default")
      (node (ref "U1") (pin "35") (pinfunction "PWM1_35") (pintype "output"))
    )
    (net (code "109") (name "unconnected-(U1-PWM2-Pad36)") (class "Default")
      (node (ref "U1") (pin "36") (pinfunction "PWM2_36") (pintype "output"))
    )
    (net (code "110") (name "unconnected-(U1-RI-Pad4)") (class "Default")
      (node (ref "U1") (pin "4") (pinfunction "RI_4") (pintype "output"))
    )
    (net (code "111") (name "unconnected-(U1-RTS-Pad8)") (class "Default")
      (node (ref "U1") (pin "8") (pinfunction "RTS_8") (pintype "input"))
    )
    (net (code "112") (name "unconnected-(U1-SCL-Pad38)") (class "Default")
      (node (ref "U1") (pin "38") (pinfunction "SCL_38") (pintype "output"))
    )
    (net (code "113") (name "unconnected-(U1-SDA-Pad37)") (class "Default")
      (node (ref "U1") (pin "37") (pinfunction "SDA_37") (pintype "bidirectional"))
    )
    (net (code "114") (name "unconnected-(U1-SIM_PRESENCE-Pad34)") (class "Default")
      (node (ref "U1") (pin "34") (pinfunction "SIM_PRESENCE_34") (pintype "passive"))
    )
    (net (code "115") (name "unconnected-(U2-SHD-Pad1)") (class "Default")
      (node (ref "U2") (pin "1") (pinfunction "SHD_1") (pintype "passive"))
    )
  )
)
